# DualDriverStepperLeft.net
KiCad netlist of a schematic drawn in Altium Designer
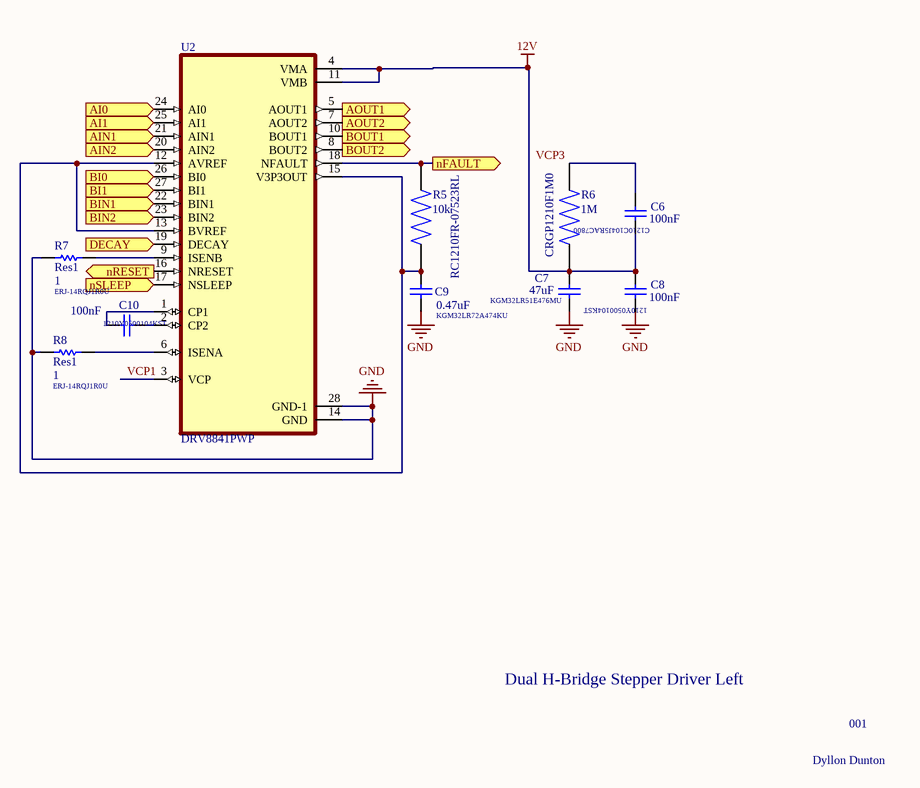
[diagram p0: DualDriverStepperLeft.SchDoc]

(export (version "E")
  (design (tool "Eeschema 10.0.6"))
  (components
    (comp (ref "C6")
      (value "100nF")
      (footprint "C1210")
      (description "Capacitor")
      (fields (field (name "Comment") "Cap") (field (name "PUBLISHER") "Altium Limited"))
      (libsource (lib "Miscellaneous Devices") (part "Cap"))
    )
    (comp (ref "C7")
      (value "47uF")
      (footprint "C1210")
      (description "Capacitor")
      (fields (field (name "Comment") "Cap") (field (name "PUBLISHER") "Altium Limited"))
      (libsource (lib "Miscellaneous Devices") (part "Cap"))
    )
    (comp (ref "C8")
      (value "100nF")
      (footprint "C1210")
      (description "Capacitor")
      (fields (field (name "Comment") "Cap") (field (name "PUBLISHER") "Altium Limited"))
      (libsource (lib "Miscellaneous Devices") (part "Cap"))
    )
    (comp (ref "C9")
      (value "0.47uF")
      (footprint "C1210")
      (description "Capacitor")
      (fields (field (name "Comment") "Cap") (field (name "PUBLISHER") "Altium Limited"))
      (libsource (lib "Miscellaneous Devices") (part "Cap"))
    )
    (comp (ref "C10")
      (value "100nF")
      (footprint "C1210")
      (description "Capacitor")
      (fields (field (name "Comment") "Cap") (field (name "PUBLISHER") "Altium Limited"))
      (libsource (lib "Miscellaneous Devices") (part "Cap"))
    )
    (comp (ref "R5")
      (value "RC1210FR-07523RL")
      (footprint "RESC3126X65N")
      (description "523 Ohms Â±1% 0.5W, 1/2W Chip Resistor 1210 _3225 Metric_ Moisture Resistant Thick Film")
      (fields (field (name "MF") "Yageo") (field (name "ALTIUM_VALUE") "10k"))
      (libsource (lib "RC1210FR-07523RL") (part "RC1210FR-07523RL"))
    )
    (comp (ref "R6")
      (value "CRGP1210F1M0")
      (footprint "RESC3126X65N")
      (description "523 Ohms Â±1% 0.5W, 1/2W Chip Resistor 1210 _3225 Metric_ Moisture Resistant Thick Film")
      (fields
        (field (name "MF") "Yageo")
        (field (name "ALTIUM_VALUE") "1M")
        (field (name "MP") "RC1210FR-07523RL")
      )
      (libsource (lib "RC1210FR-07523RL") (part "RC1210FR-07523RL"))
    )
    (comp (ref "R7")
      (value "Res1")
      (footprint "RES_ERJ14RQJ1R0U")
      (description "Resistor")
      (fields (field (name "ALTIUM_VALUE") "1") (field (name "PUBLISHER") "Altium Limited"))
      (libsource (lib "Miscellaneous Devices") (part "Res1"))
    )
    (comp (ref "R8")
      (value "Res1")
      (footprint "RES_ERJ14RQJ1R0U")
      (description "Resistor")
      (fields (field (name "ALTIUM_VALUE") "1") (field (name "PUBLISHER") "Altium Limited"))
      (libsource (lib "Miscellaneous Devices") (part "Res1"))
    )
    (comp (ref "U2")
      (value "DRV8841PWP")
      (footprint "IC_TPS61196PWPRQ1")
      (fields (field (name "MF") "Texas Instruments"))
      (libsource (lib "DRV8841PWP") (part "DRV8841PWP"))
    )
  )
  (nets
    (net (code "1") (name "/AI0") (class "Default")
      (node (ref "U2") (pin "24") (pinfunction "AI0_24") (pintype "input"))
    )
    (net (code "2") (name "/AI1") (class "Default")
      (node (ref "U2") (pin "25") (pinfunction "AI1_25") (pintype "input"))
    )
    (net (code "3") (name "/AIN1") (class "Default")
      (node (ref "U2") (pin "21") (pinfunction "AIN1_21") (pintype "input"))
    )
    (net (code "4") (name "/AIN2") (class "Default")
      (node (ref "U2") (pin "20") (pinfunction "AIN2_20") (pintype "input"))
    )
    (net (code "5") (name "/AOUT1") (class "Default")
      (node (ref "U2") (pin "5") (pinfunction "AOUT1_5") (pintype "output"))
    )
    (net (code "6") (name "/AOUT2") (class "Default")
      (node (ref "U2") (pin "7") (pinfunction "AOUT2_7") (pintype "output"))
    )
    (net (code "7") (name "/BI0") (class "Default")
      (node (ref "U2") (pin "26") (pinfunction "BI0_26") (pintype "input"))
    )
    (net (code "8") (name "/BI1") (class "Default")
      (node (ref "U2") (pin "27") (pinfunction "BI1_27") (pintype "input"))
    )
    (net (code "9") (name "/BIN1") (class "Default")
      (node (ref "U2") (pin "22") (pinfunction "BIN1_22") (pintype "input"))
    )
    (net (code "10") (name "/BIN2") (class "Default")
      (node (ref "U2") (pin "23") (pinfunction "BIN2_23") (pintype "input"))
    )
    (net (code "11") (name "/BOUT1") (class "Default")
      (node (ref "U2") (pin "10") (pinfunction "BOUT1_10") (pintype "output"))
    )
    (net (code "12") (name "/BOUT2") (class "Default")
      (node (ref "U2") (pin "8") (pinfunction "BOUT2_8") (pintype "output"))
    )
    (net (code "13") (name "/DECAY") (class "Default")
      (node (ref "U2") (pin "19") (pinfunction "DECAY_19") (pintype "input"))
    )
    (net (code "14") (name "/VCP1") (class "Default")
      (node (ref "U2") (pin "3") (pinfunction "VCP_3") (pintype "bidirectional"))
    )
    (net (code "16") (name "/nFAULT") (class "Default")
      (node (ref "R5") (pin "2") (pinfunction "2_2") (pintype "passive"))
      (node (ref "U2") (pin "18") (pinfunction "NFAULT_18") (pintype "output"))
    )
    (net (code "17") (name "/nRESET") (class "Default")
      (node (ref "U2") (pin "16") (pinfunction "NRESET_16") (pintype "input"))
    )
    (net (code "18") (name "/nSLEEP") (class "Default")
      (node (ref "U2") (pin "17") (pinfunction "NSLEEP_17") (pintype "input"))
    )
    (net (code "19") (name "12V") (class "Default")
      (node (ref "C6") (pin "2") (pinfunction "2_2") (pintype "passive"))
      (node (ref "C7") (pin "2") (pinfunction "2_2") (pintype "passive"))
      (node (ref "C8") (pin "1") (pinfunction "1_1") (pintype "passive"))
      (node (ref "R6") (pin "1") (pinfunction "1_1") (pintype "passive"))
      (node (ref "U2") (pin "11") (pinfunction "VMB_11") (pintype "power_in"))
      (node (ref "U2") (pin "4") (pinfunction "VMA_4") (pintype "power_in"))
    )
    (net (code "20") (name "GND") (class "Default")
      (node (ref "C7") (pin "1") (pinfunction "1_1") (pintype "passive"))
      (node (ref "C8") (pin "2") (pinfunction "2_2") (pintype "passive"))
      (node (ref "C9") (pin "1") (pinfunction "1_1") (pintype "passive"))
      (node (ref "R7") (pin "1") (pinfunction "1_1") (pintype "passive"))
      (node (ref "R8") (pin "1") (pinfunction "1_1") (pintype "passive"))
      (node (ref "U2") (pin "14") (pinfunction "GND_14") (pintype "power_in"))
      (node (ref "U2") (pin "28") (pinfunction "GND-1_28") (pintype "power_in"))
    )
    (net (code "21") (name "Net-(C6-Pad1)") (class "Default")
      (node (ref "C6") (pin "1") (pinfunction "1_1") (pintype "passive"))
      (node (ref "R6") (pin "2") (pinfunction "2_2") (pintype "passive"))
    )
    (net (code "22") (name "Net-(U2-AVREF)") (class "Default")
      (node (ref "C9") (pin "2") (pinfunction "2_2") (pintype "passive"))
      (node (ref "R5") (pin "1") (pinfunction "1_1") (pintype "passive"))
      (node (ref "U2") (pin "12") (pinfunction "AVREF_12") (pintype "input"))
      (node (ref "U2") (pin "13") (pinfunction "BVREF_13") (pintype "input"))
      (node (ref "U2") (pin "15") (pinfunction "V3P3OUT_15") (pintype "output"))
    )
    (net (code "23") (name "Net-(U2-CP1)") (class "Default")
      (node (ref "C10") (pin "2") (pinfunction "2_2") (pintype "passive"))
      (node (ref "U2") (pin "1") (pinfunction "CP1_1") (pintype "bidirectional"))
    )
    (net (code "24") (name "Net-(U2-CP2)") (class "Default")
      (node (ref "C10") (pin "1") (pinfunction "1_1") (pintype "passive"))
      (node (ref "U2") (pin "2") (pinfunction "CP2_2") (pintype "bidirectional"))
    )
    (net (code "25") (name "Net-(U2-ISENA)") (class "Default")
      (node (ref "R8") (pin "2") (pinfunction "2_2") (pintype "passive"))
      (node (ref "U2") (pin "6") (pinfunction "ISENA_6") (pintype "bidirectional"))
    )
    (net (code "26") (name "Net-(U2-ISENB)") (class "Default")
      (node (ref "R7") (pin "2") (pinfunction "2_2") (pintype "passive"))
      (node (ref "U2") (pin "9") (pinfunction "ISENB_9") (pintype "input"))
    )
  )
)
